# distance.net
KiCad netlist of a schematic drawn in EAGLE
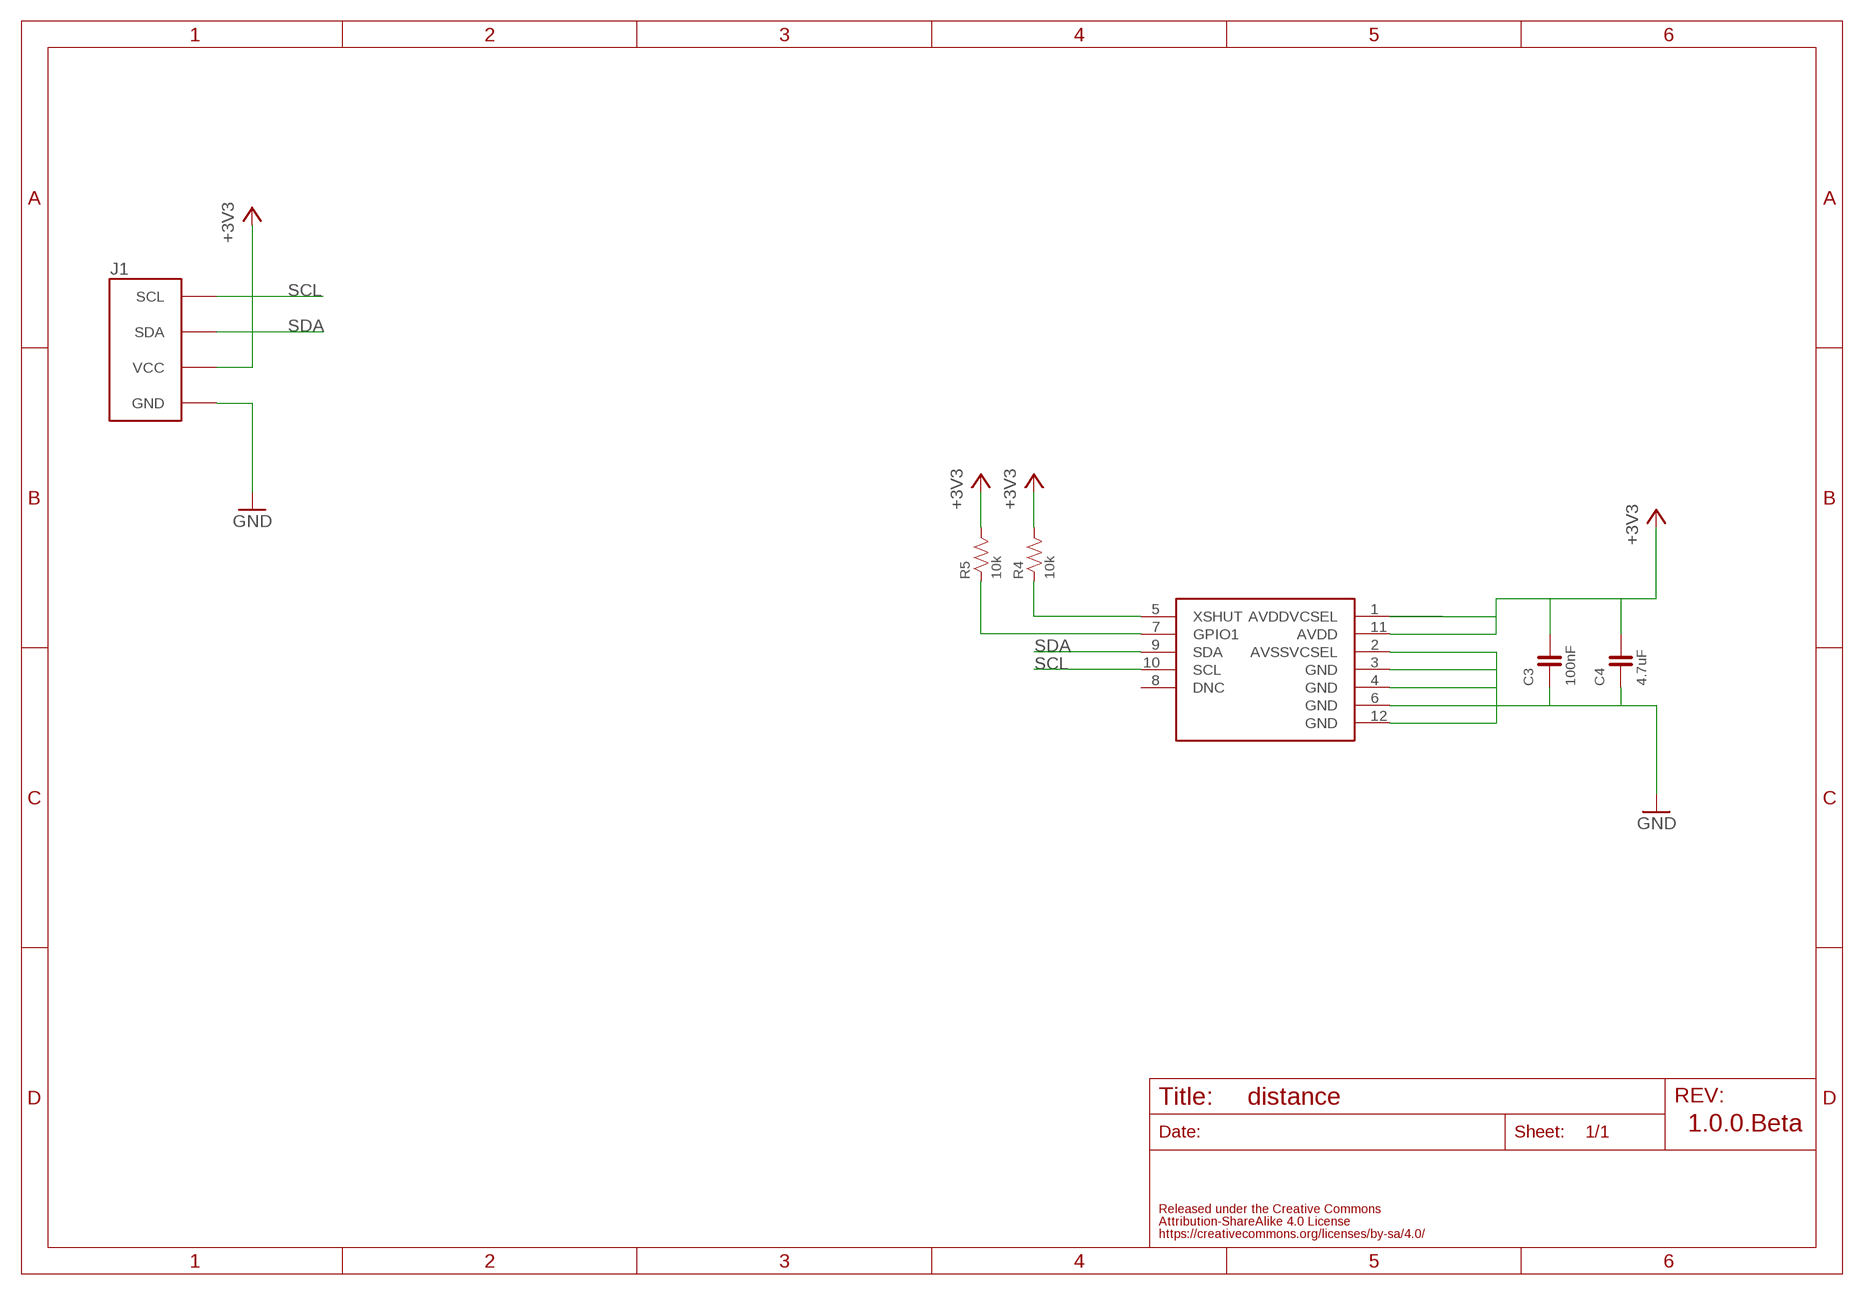
[diagram p0: schematic, sheet 1]

(export (version "E")
  (design (tool "Eeschema 10.0.6"))
  (components
    (comp (ref "C3")
      (value "100nF")
      (footprint "eagle-import:0603")
      (libsource (lib "eagle-import") (part "CAPACITOR-0603"))
    )
    (comp (ref "C4")
      (value "4.7uF")
      (footprint "eagle-import:0603")
      (libsource (lib "eagle-import") (part "CAPACITOR-0603"))
    )
    (comp (ref "J1")
      (value "FABO_BRICK_I2C-B04B-PASK-1_SILK_BOTTOM")
      (footprint "eagle-import:FABO_BRICK_I2C_B04B-PASK-1_SILK_BOTTOM")
      (libsource (lib "eagle-import") (part "FABO_BRICK_I2C-B04B-PASK-1_SILK_BOTTOM"))
    )
    (comp (ref "R4")
      (value "10k")
      (footprint "eagle-import:0603")
      (libsource (lib "eagle-import") (part "RESISTOR-0603"))
    )
    (comp (ref "R5")
      (value "10k")
      (footprint "eagle-import:0603")
      (libsource (lib "eagle-import") (part "RESISTOR-0603"))
    )
    (comp (ref "VL1")
      (value "ST-VL53L0XVL53")
      (footprint "eagle-import:ST-VL53L0X")
      (libsource (lib "eagle-import") (part "ST-VL53L0XVL53"))
    )
  )
  (nets
    (net (code "1") (name "+3V3") (class "Default")
      (node (ref "C3") (pin "2") (pinfunction "2_2") (pintype "passive"))
      (node (ref "C4") (pin "2") (pinfunction "2_2") (pintype "passive"))
      (node (ref "J1") (pin "VCC") (pinfunction "VCC_VCC") (pintype "bidirectional"))
      (node (ref "R4") (pin "2") (pinfunction "2_2") (pintype "bidirectional"))
      (node (ref "R5") (pin "2") (pinfunction "2_2") (pintype "bidirectional"))
      (node (ref "VL1") (pin "1") (pinfunction "AVDDVCSEL_1") (pintype "bidirectional"))
      (node (ref "VL1") (pin "11") (pinfunction "AVDD_11") (pintype "bidirectional"))
    )
    (net (code "2") (name "/SCL") (class "Default")
      (node (ref "J1") (pin "SCL") (pinfunction "SCL_SCL") (pintype "bidirectional"))
      (node (ref "VL1") (pin "10") (pinfunction "SCL_10") (pintype "bidirectional"))
    )
    (net (code "3") (name "/SDA") (class "Default")
      (node (ref "J1") (pin "SDA") (pinfunction "SDA_SDA") (pintype "bidirectional"))
      (node (ref "VL1") (pin "9") (pinfunction "SDA_9") (pintype "bidirectional"))
    )
    (net (code "4") (name "GND") (class "Default")
      (node (ref "C3") (pin "1") (pinfunction "1_1") (pintype "passive"))
      (node (ref "C4") (pin "1") (pinfunction "1_1") (pintype "passive"))
      (node (ref "J1") (pin "GND") (pinfunction "GND_GND") (pintype "bidirectional"))
      (node (ref "VL1") (pin "12") (pinfunction "GND_12") (pintype "bidirectional"))
      (node (ref "VL1") (pin "2") (pinfunction "AVSSVCSEL_2") (pintype "bidirectional"))
      (node (ref "VL1") (pin "3") (pinfunction "GND_3") (pintype "bidirectional"))
      (node (ref "VL1") (pin "4") (pinfunction "GND_4") (pintype "bidirectional"))
      (node (ref "VL1") (pin "6") (pinfunction "GND_6") (pintype "bidirectional"))
    )
    (net (code "5") (name "Net-(VL1-GPIO1)") (class "Default")
      (node (ref "R5") (pin "1") (pinfunction "1_1") (pintype "bidirectional"))
      (node (ref "VL1") (pin "7") (pinfunction "GPIO1_7") (pintype "bidirectional"))
    )
    (net (code "6") (name "Net-(VL1-XSHUT)") (class "Default")
      (node (ref "R4") (pin "1") (pinfunction "1_1") (pintype "bidirectional"))
      (node (ref "VL1") (pin "5") (pinfunction "XSHUT_5") (pintype "bidirectional"))
    )
    (net (code "7") (name "unconnected-(VL1-DNC-Pad8)") (class "Default")
      (node (ref "VL1") (pin "8") (pinfunction "DNC_8") (pintype "bidirectional"))
    )
  )
)
